# System_critical_signals_PCB.net
KiCad netlist of a schematic drawn in EAGLE
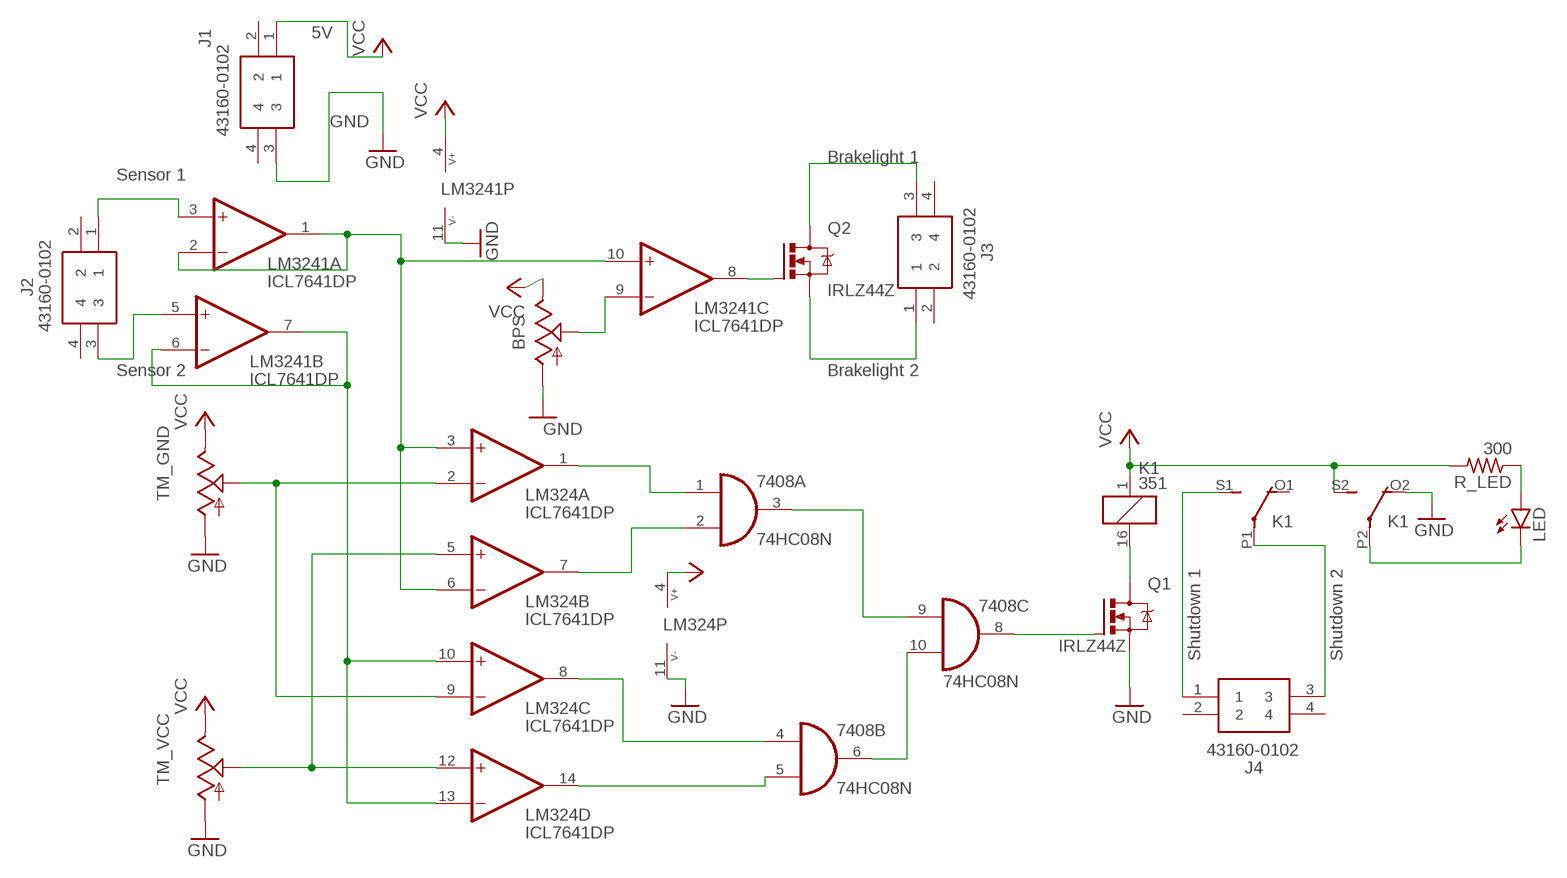
[diagram p0: schematic, sheet 1]

(export (version "E")
  (design (tool "Eeschema 10.0.6"))
  (components
    (comp (ref "7408")
      (value "74HC08N")
      (footprint "eagle-import:DIL14")
      (libsource (lib "eagle-import") (part "7408NHC"))
    )
    (comp (ref "BPS")
      (value "TRIM")
      (footprint "eagle-import:6MM")
      (libsource (lib "eagle-import") (part "TRIM"))
    )
    (comp (ref "J1")
      (value "43160-0102")
      (footprint "eagle-import:431600102")
      (fields (field (name "MOUSER_PART_NUMBER") "538-43160-0102"))
      (libsource (lib "eagle-import") (part "43160-0102"))
    )
    (comp (ref "J2")
      (value "43160-0102")
      (footprint "eagle-import:431600102")
      (fields (field (name "MOUSER_PART_NUMBER") "538-43160-0102"))
      (libsource (lib "eagle-import") (part "43160-0102"))
    )
    (comp (ref "J3")
      (value "43160-0102")
      (footprint "eagle-import:431600102")
      (fields (field (name "MOUSER_PART_NUMBER") "538-43160-0102"))
      (libsource (lib "eagle-import") (part "43160-0102"))
    )
    (comp (ref "J4")
      (value "43160-0102")
      (footprint "eagle-import:431600102")
      (fields (field (name "MOUSER_PART_NUMBER") "538-43160-0102"))
      (libsource (lib "eagle-import") (part "43160-0102"))
    )
    (comp (ref "K1")
      (value "351")
      (footprint "eagle-import:351")
      (libsource (lib "eagle-import") (part "351"))
    )
    (comp (ref "LED")
      (value "LEDCHIP-LED0805")
      (footprint "eagle-import:CHIP-LED0805")
      (libsource (lib "eagle-import") (part "LEDCHIP-LED0805"))
    )
    (comp (ref "LM324")
      (value "ICL7641DP")
      (footprint "eagle-import:DIL14")
      (libsource (lib "eagle-import") (part "ICL764DP1"))
    )
    (comp (ref "LM3241")
      (value "ICL7641DP")
      (footprint "eagle-import:DIL14")
      (libsource (lib "eagle-import") (part "ICL764DP1"))
    )
    (comp (ref "Q1")
      (value "IRLZ44Z")
      (footprint "eagle-import:TO220BH")
      (libsource (lib "eagle-import") (part "IRLZ44Z"))
    )
    (comp (ref "Q2")
      (value "IRLZ44Z")
      (footprint "eagle-import:TO220BH")
      (libsource (lib "eagle-import") (part "IRLZ44Z"))
    )
    (comp (ref "R_LED")
      (value "300")
      (footprint "eagle-import:M0805")
      (libsource (lib "eagle-import") (part "R-US_M0805"))
    )
    (comp (ref "TM_GND")
      (value "TRIM")
      (footprint "eagle-import:6MM")
      (libsource (lib "eagle-import") (part "TRIM"))
    )
    (comp (ref "TM_VCC")
      (value "TRIM")
      (footprint "eagle-import:6MM")
      (libsource (lib "eagle-import") (part "TRIM"))
    )
  )
  (nets
    (net (code "1") (name "GND") (class "Default")
      (node (ref "BPS") (pin "A") (pinfunction "A_A") (pintype "passive"))
      (node (ref "J1") (pin "3") (pinfunction "3_3") (pintype "bidirectional"))
      (node (ref "K1") (pin "O2") (pinfunction "O_O2") (pintype "passive"))
      (node (ref "LM324") (pin "11") (pinfunction "V-_11") (pintype "power_in"))
      (node (ref "LM3241") (pin "11") (pinfunction "V-_11") (pintype "power_in"))
      (node (ref "Q1") (pin "S") (pinfunction "S_S") (pintype "passive"))
      (node (ref "TM_GND") (pin "A") (pinfunction "A_A") (pintype "passive"))
      (node (ref "TM_VCC") (pin "A") (pinfunction "A_A") (pintype "passive"))
    )
    (net (code "2") (name "Net-(7408A-I0)") (class "Default")
      (node (ref "7408") (pin "1") (pinfunction "I0_1") (pintype "input"))
      (node (ref "LM324") (pin "1") (pinfunction "OUT_1") (pintype "output"))
    )
    (net (code "3") (name "Net-(7408A-I1)") (class "Default")
      (node (ref "7408") (pin "2") (pinfunction "I1_2") (pintype "input"))
      (node (ref "LM324") (pin "7") (pinfunction "OUT_7") (pintype "output"))
    )
    (net (code "4") (name "Net-(7408A-O)") (class "Default")
      (node (ref "7408") (pin "3") (pinfunction "O_3") (pintype "output"))
      (node (ref "7408") (pin "9") (pinfunction "I0_9") (pintype "input"))
    )
    (net (code "5") (name "Net-(7408B-I0)") (class "Default")
      (node (ref "7408") (pin "4") (pinfunction "I0_4") (pintype "input"))
      (node (ref "LM324") (pin "8") (pinfunction "OUT_8") (pintype "output"))
    )
    (net (code "6") (name "Net-(7408B-I1)") (class "Default")
      (node (ref "7408") (pin "5") (pinfunction "I1_5") (pintype "input"))
      (node (ref "LM324") (pin "14") (pinfunction "OUT_14") (pintype "output"))
    )
    (net (code "7") (name "Net-(7408B-O)") (class "Default")
      (node (ref "7408") (pin "10") (pinfunction "I1_10") (pintype "input"))
      (node (ref "7408") (pin "6") (pinfunction "O_6") (pintype "output"))
    )
    (net (code "8") (name "Net-(7408C-O)") (class "Default")
      (node (ref "7408") (pin "8") (pinfunction "O_8") (pintype "output"))
      (node (ref "Q1") (pin "G") (pinfunction "G_G") (pintype "passive"))
    )
    (net (code "9") (name "Net-(J3-Pad1)") (class "Default")
      (node (ref "J3") (pin "1") (pinfunction "1_1") (pintype "bidirectional"))
      (node (ref "Q2") (pin "S") (pinfunction "S_S") (pintype "passive"))
    )
    (net (code "10") (name "Net-(J3-Pad3)") (class "Default")
      (node (ref "J3") (pin "3") (pinfunction "3_3") (pintype "bidirectional"))
      (node (ref "Q2") (pin "D") (pinfunction "D_D") (pintype "passive"))
    )
    (net (code "11") (name "Net-(K1A-2)") (class "Default")
      (node (ref "K1") (pin "16") (pinfunction "2_16") (pintype "passive"))
      (node (ref "Q1") (pin "D") (pinfunction "D_D") (pintype "passive"))
    )
    (net (code "12") (name "Net-(K1B-P)") (class "Default")
      (node (ref "J4") (pin "3") (pinfunction "3_3") (pintype "bidirectional"))
      (node (ref "K1") (pin "P1") (pinfunction "P_P1") (pintype "passive"))
    )
    (net (code "13") (name "Net-(K1B-S)") (class "Default")
      (node (ref "J4") (pin "1") (pinfunction "1_1") (pintype "bidirectional"))
      (node (ref "K1") (pin "S1") (pinfunction "S_S1") (pintype "passive"))
    )
    (net (code "14") (name "Net-(K1C-P)") (class "Default")
      (node (ref "K1") (pin "P2") (pinfunction "P_P2") (pintype "passive"))
      (node (ref "LED") (pin "C") (pinfunction "C_C") (pintype "passive"))
    )
    (net (code "15") (name "Net-(LED-PadA)") (class "Default")
      (node (ref "LED") (pin "A") (pinfunction "A_A") (pintype "passive"))
      (node (ref "R_LED") (pin "1") (pinfunction "1_1") (pintype "passive"))
    )
    (net (code "16") (name "Net-(LM324A--IN)") (class "Default")
      (node (ref "LM324") (pin "2") (pinfunction "-IN_2") (pintype "input"))
      (node (ref "LM324") (pin "9") (pinfunction "-IN_9") (pintype "input"))
      (node (ref "TM_GND") (pin "S") (pinfunction "S_S") (pintype "passive"))
    )
    (net (code "17") (name "Net-(LM324B-+IN)") (class "Default")
      (node (ref "LM324") (pin "12") (pinfunction "+IN_12") (pintype "input"))
      (node (ref "LM324") (pin "5") (pinfunction "+IN_5") (pintype "input"))
      (node (ref "TM_VCC") (pin "S") (pinfunction "S_S") (pintype "passive"))
    )
    (net (code "18") (name "Net-(LM3241A-+IN)") (class "Default")
      (node (ref "J2") (pin "1") (pinfunction "1_1") (pintype "bidirectional"))
      (node (ref "LM3241") (pin "3") (pinfunction "+IN_3") (pintype "input"))
    )
    (net (code "19") (name "Net-(LM3241A--IN)") (class "Default")
      (node (ref "LM324") (pin "3") (pinfunction "+IN_3") (pintype "input"))
      (node (ref "LM324") (pin "6") (pinfunction "-IN_6") (pintype "input"))
      (node (ref "LM3241") (pin "1") (pinfunction "OUT_1") (pintype "output"))
      (node (ref "LM3241") (pin "10") (pinfunction "+IN_10") (pintype "input"))
      (node (ref "LM3241") (pin "2") (pinfunction "-IN_2") (pintype "input"))
    )
    (net (code "20") (name "Net-(LM3241B-+IN)") (class "Default")
      (node (ref "J2") (pin "3") (pinfunction "3_3") (pintype "bidirectional"))
      (node (ref "LM3241") (pin "5") (pinfunction "+IN_5") (pintype "input"))
    )
    (net (code "21") (name "Net-(LM3241B--IN)") (class "Default")
      (node (ref "LM324") (pin "10") (pinfunction "+IN_10") (pintype "input"))
      (node (ref "LM324") (pin "13") (pinfunction "-IN_13") (pintype "input"))
      (node (ref "LM3241") (pin "6") (pinfunction "-IN_6") (pintype "input"))
      (node (ref "LM3241") (pin "7") (pinfunction "OUT_7") (pintype "output"))
    )
    (net (code "22") (name "Net-(LM3241C--IN)") (class "Default")
      (node (ref "BPS") (pin "S") (pinfunction "S_S") (pintype "passive"))
      (node (ref "LM3241") (pin "9") (pinfunction "-IN_9") (pintype "input"))
    )
    (net (code "23") (name "Net-(LM3241C-OUT)") (class "Default")
      (node (ref "LM3241") (pin "8") (pinfunction "OUT_8") (pintype "output"))
      (node (ref "Q2") (pin "G") (pinfunction "G_G") (pintype "passive"))
    )
    (net (code "24") (name "VCC") (class "Default")
      (node (ref "BPS") (pin "E") (pinfunction "E_E") (pintype "passive"))
      (node (ref "J1") (pin "1") (pinfunction "1_1") (pintype "bidirectional"))
      (node (ref "K1") (pin "1") (pinfunction "1_1") (pintype "passive"))
      (node (ref "K1") (pin "S2") (pinfunction "S_S2") (pintype "passive"))
      (node (ref "LM324") (pin "4") (pinfunction "V+_4") (pintype "power_in"))
      (node (ref "LM3241") (pin "4") (pinfunction "V+_4") (pintype "power_in"))
      (node (ref "R_LED") (pin "2") (pinfunction "2_2") (pintype "passive"))
      (node (ref "TM_GND") (pin "E") (pinfunction "E_E") (pintype "passive"))
      (node (ref "TM_VCC") (pin "E") (pinfunction "E_E") (pintype "passive"))
    )
    (net (code "25") (name "unconnected-(J1-Pad2)") (class "Default")
      (node (ref "J1") (pin "2") (pinfunction "2_2") (pintype "bidirectional"))
    )
    (net (code "26") (name "unconnected-(J1-Pad4)") (class "Default")
      (node (ref "J1") (pin "4") (pinfunction "4_4") (pintype "bidirectional"))
    )
    (net (code "27") (name "unconnected-(J2-Pad2)") (class "Default")
      (node (ref "J2") (pin "2") (pinfunction "2_2") (pintype "bidirectional"))
    )
    (net (code "28") (name "unconnected-(J2-Pad4)") (class "Default")
      (node (ref "J2") (pin "4") (pinfunction "4_4") (pintype "bidirectional"))
    )
    (net (code "29") (name "unconnected-(J3-Pad2)") (class "Default")
      (node (ref "J3") (pin "2") (pinfunction "2_2") (pintype "bidirectional"))
    )
    (net (code "30") (name "unconnected-(J3-Pad4)") (class "Default")
      (node (ref "J3") (pin "4") (pinfunction "4_4") (pintype "bidirectional"))
    )
    (net (code "31") (name "unconnected-(J4-Pad2)") (class "Default")
      (node (ref "J4") (pin "2") (pinfunction "2_2") (pintype "bidirectional"))
    )
    (net (code "32") (name "unconnected-(J4-Pad4)") (class "Default")
      (node (ref "J4") (pin "4") (pinfunction "4_4") (pintype "bidirectional"))
    )
    (net (code "33") (name "unconnected-(K1B-O-PadO1)") (class "Default")
      (node (ref "K1") (pin "O1") (pinfunction "O_O1") (pintype "passive"))
    )
  )
)
